# Top_Sheet_Power_System.net
KiCad netlist of a schematic drawn in Altium Designer
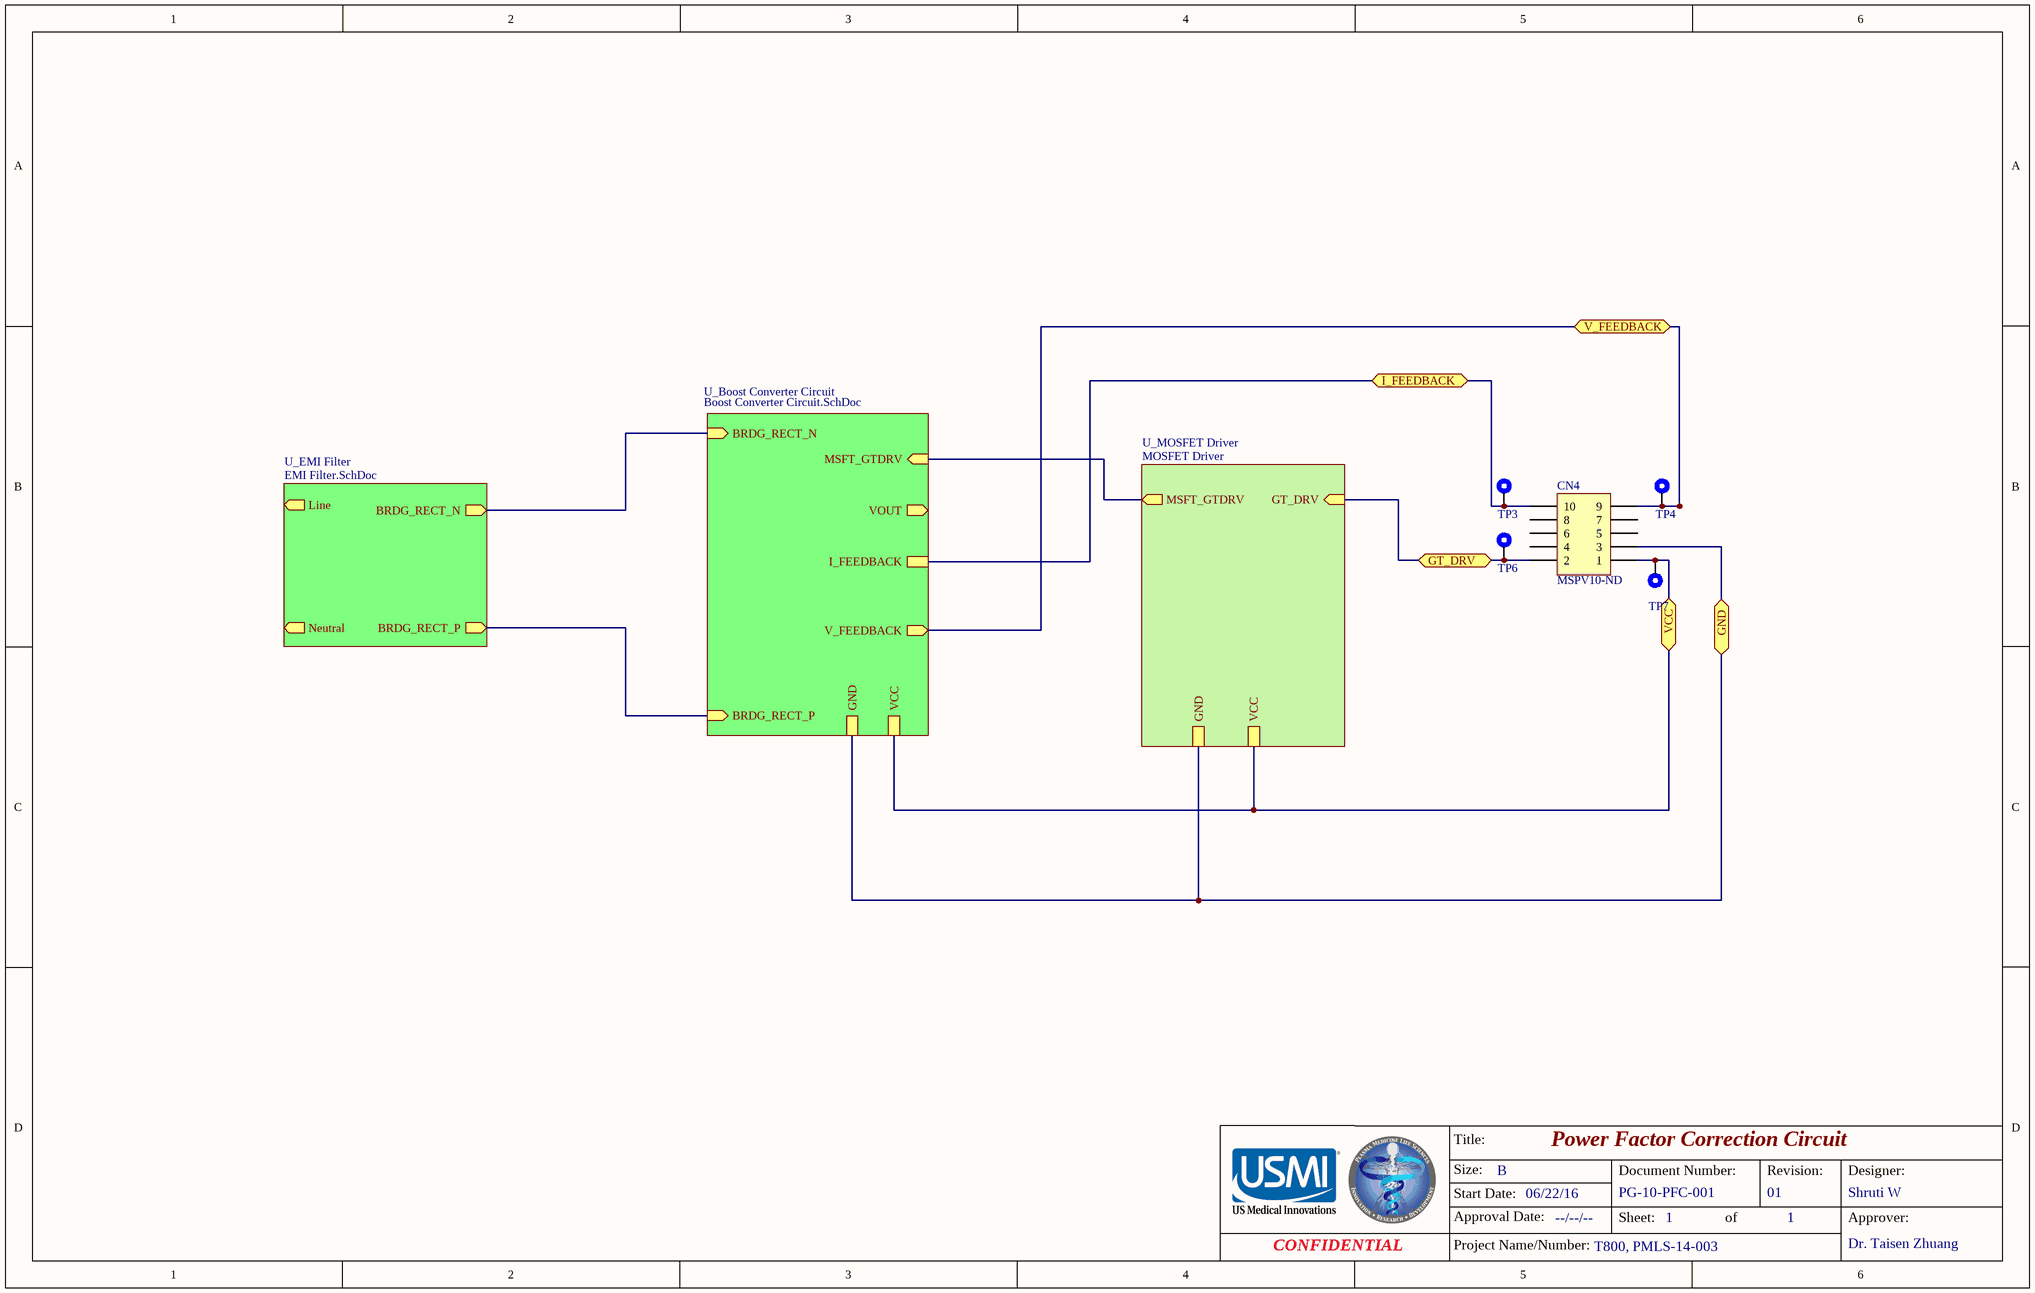
[diagram p0: Top Sheet_Power System.SchDoc]

(export (version "E")
  (design (tool "Eeschema 10.0.6"))
  (components
    (comp (ref "CN4")
      (value "MSPV10-ND")
      (footprint "MSV10-ND")
      (description "CONN SOCKET PCB VERT 10POS .1\"")
      (fields
        (field (name "MANUFACTURER") "3M")
        (field (name "MANUFACTURER PART NUMBER") "8510-4500PL")
        (field (name "SUPPLIER PART NUMBER 1") "MSPV10-ND")
      )
      (libsource (lib "ucc28180-V03") (part "MSPV10-ND"))
    )
    (comp (ref "TP3")
      (value "5006")
      (footprint "Test Point")
      (description "TEST POINT PC COMPACT .063\"D BLK")
      (libsource (lib "ucc28180-V03") (part "5006"))
    )
    (comp (ref "TP4")
      (value "5006")
      (footprint "Test Point")
      (description "TEST POINT PC COMPACT .063\"D BLK")
      (libsource (lib "ucc28180-V03") (part "5006"))
    )
    (comp (ref "TP6")
      (value "5006")
      (footprint "Test Point")
      (description "TEST POINT PC COMPACT .063\"D BLK")
      (libsource (lib "ucc28180-V03") (part "5006"))
    )
    (comp (ref "TP7")
      (value "5006")
      (footprint "Test Point")
      (description "TEST POINT PC COMPACT .063\"D BLK")
      (libsource (lib "ucc28180-V03") (part "5006"))
    )
  )
  (nets
    (net (code "3") (name "/GND") (class "Default")
      (node (ref "CN4") (pin "3") (pinfunction "3_3") (pintype "passive"))
    )
    (net (code "4") (name "/GT_DRV") (class "Default")
      (node (ref "CN4") (pin "2") (pinfunction "2_2") (pintype "passive"))
      (node (ref "TP6") (pin "1") (pinfunction "1_1") (pintype "passive"))
    )
    (net (code "5") (name "/I_FEEDBACK") (class "Default")
      (node (ref "CN4") (pin "10") (pinfunction "10_10") (pintype "passive"))
      (node (ref "TP3") (pin "1") (pinfunction "1_1") (pintype "passive"))
    )
    (net (code "9") (name "/VCC") (class "Default")
      (node (ref "CN4") (pin "1") (pinfunction "1_1") (pintype "passive"))
      (node (ref "TP7") (pin "1") (pinfunction "1_1") (pintype "passive"))
    )
    (net (code "11") (name "/V_FEEDBACK") (class "Default")
      (node (ref "CN4") (pin "9") (pinfunction "9_9") (pintype "passive"))
      (node (ref "TP4") (pin "1") (pinfunction "1_1") (pintype "passive"))
    )
    (net (code "12") (name "unconnected-(CN4-Pad4)") (class "Default")
      (node (ref "CN4") (pin "4") (pinfunction "4_4") (pintype "passive"))
    )
    (net (code "13") (name "unconnected-(CN4-Pad5)") (class "Default")
      (node (ref "CN4") (pin "5") (pinfunction "5_5") (pintype "passive"))
    )
    (net (code "14") (name "unconnected-(CN4-Pad6)") (class "Default")
      (node (ref "CN4") (pin "6") (pinfunction "6_6") (pintype "passive"))
    )
    (net (code "15") (name "unconnected-(CN4-Pad7)") (class "Default")
      (node (ref "CN4") (pin "7") (pinfunction "7_7") (pintype "passive"))
    )
    (net (code "16") (name "unconnected-(CN4-Pad8)") (class "Default")
      (node (ref "CN4") (pin "8") (pinfunction "8_8") (pintype "passive"))
    )
  )
)
